# cnc.net
KiCad netlist of a schematic drawn in EAGLE
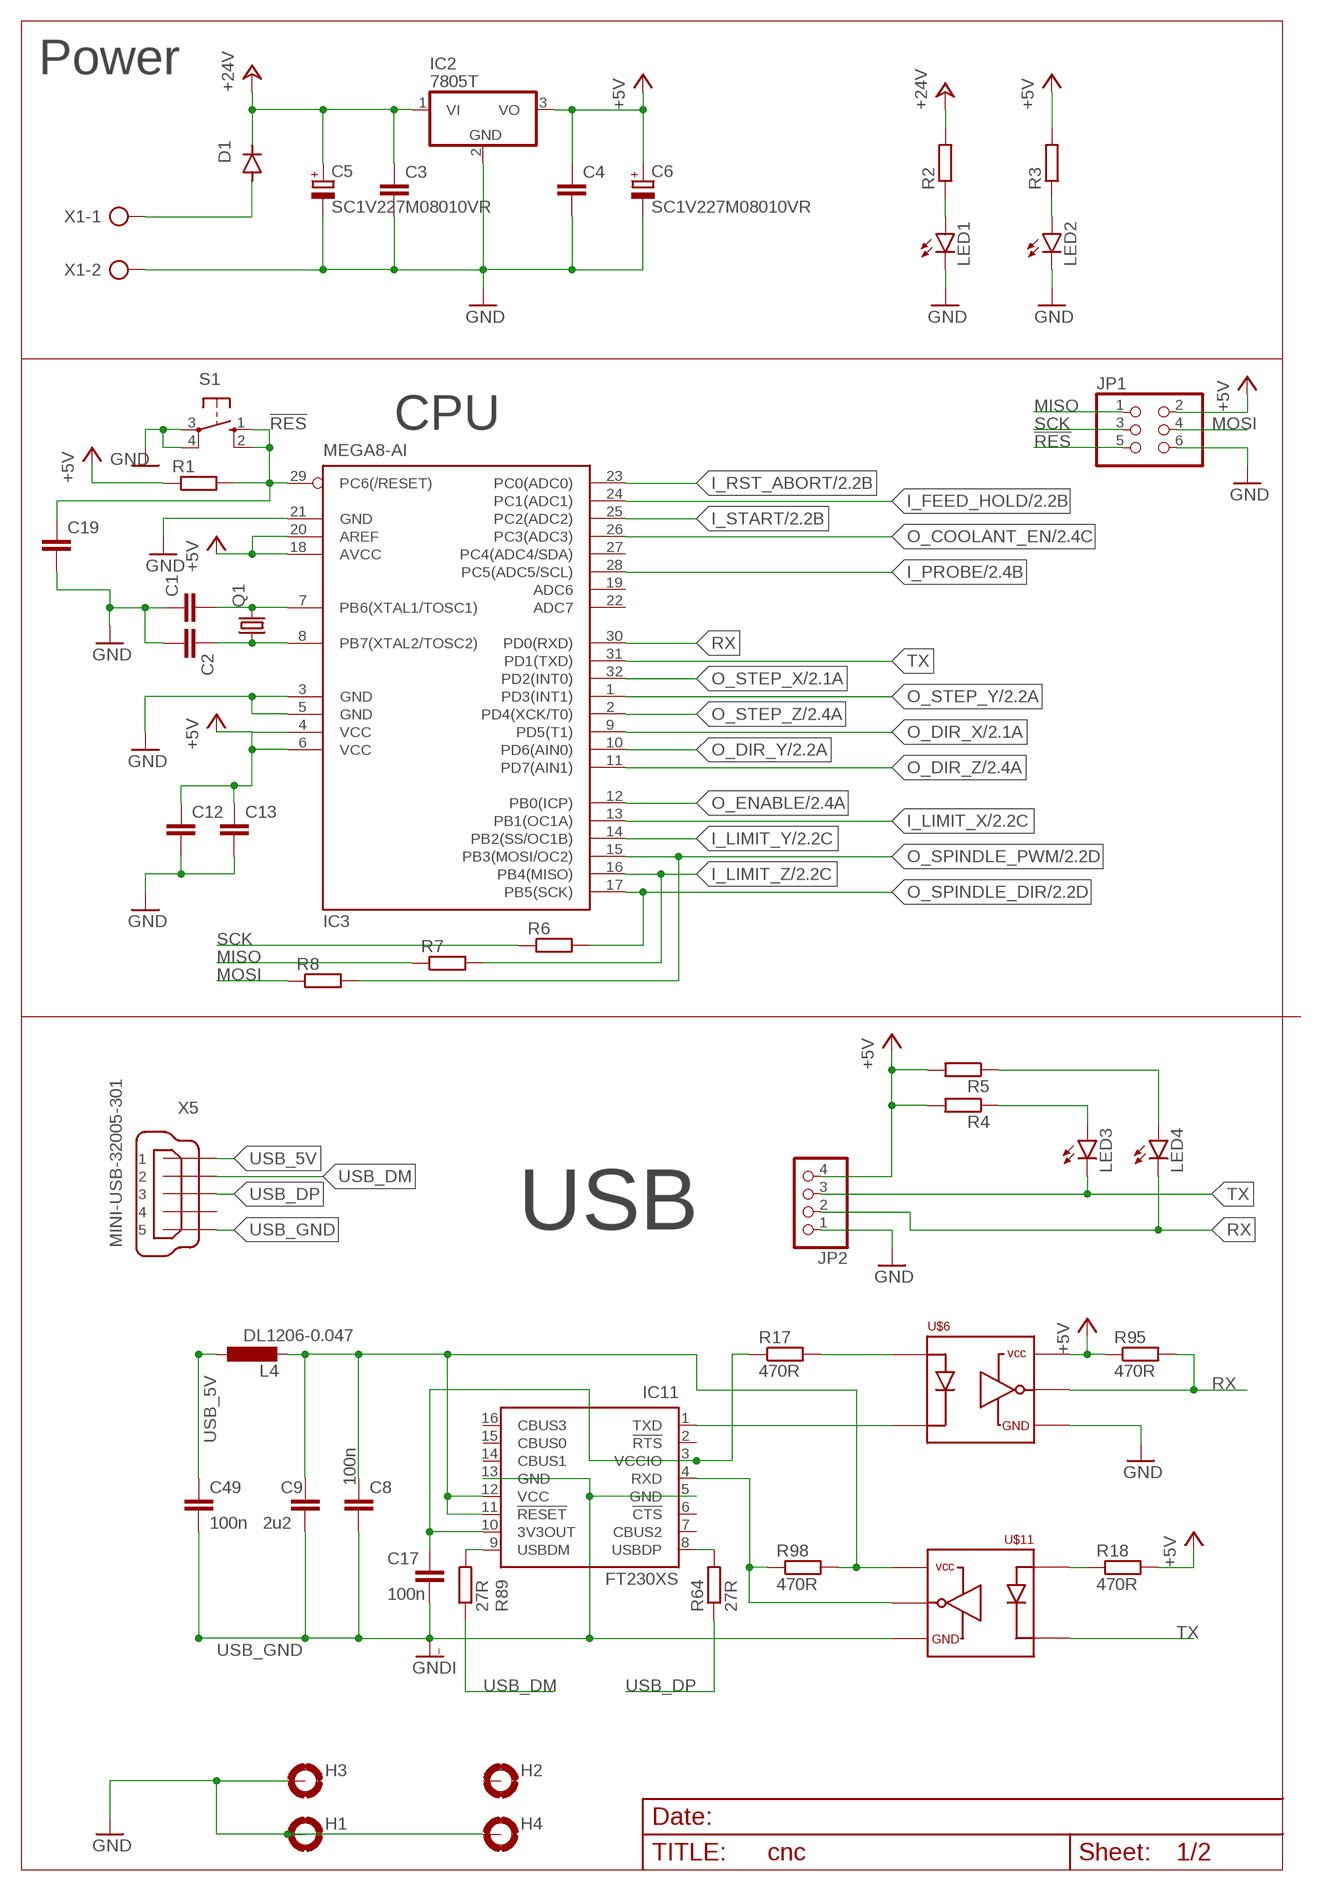
[diagram p0: schematic, sheet 1]
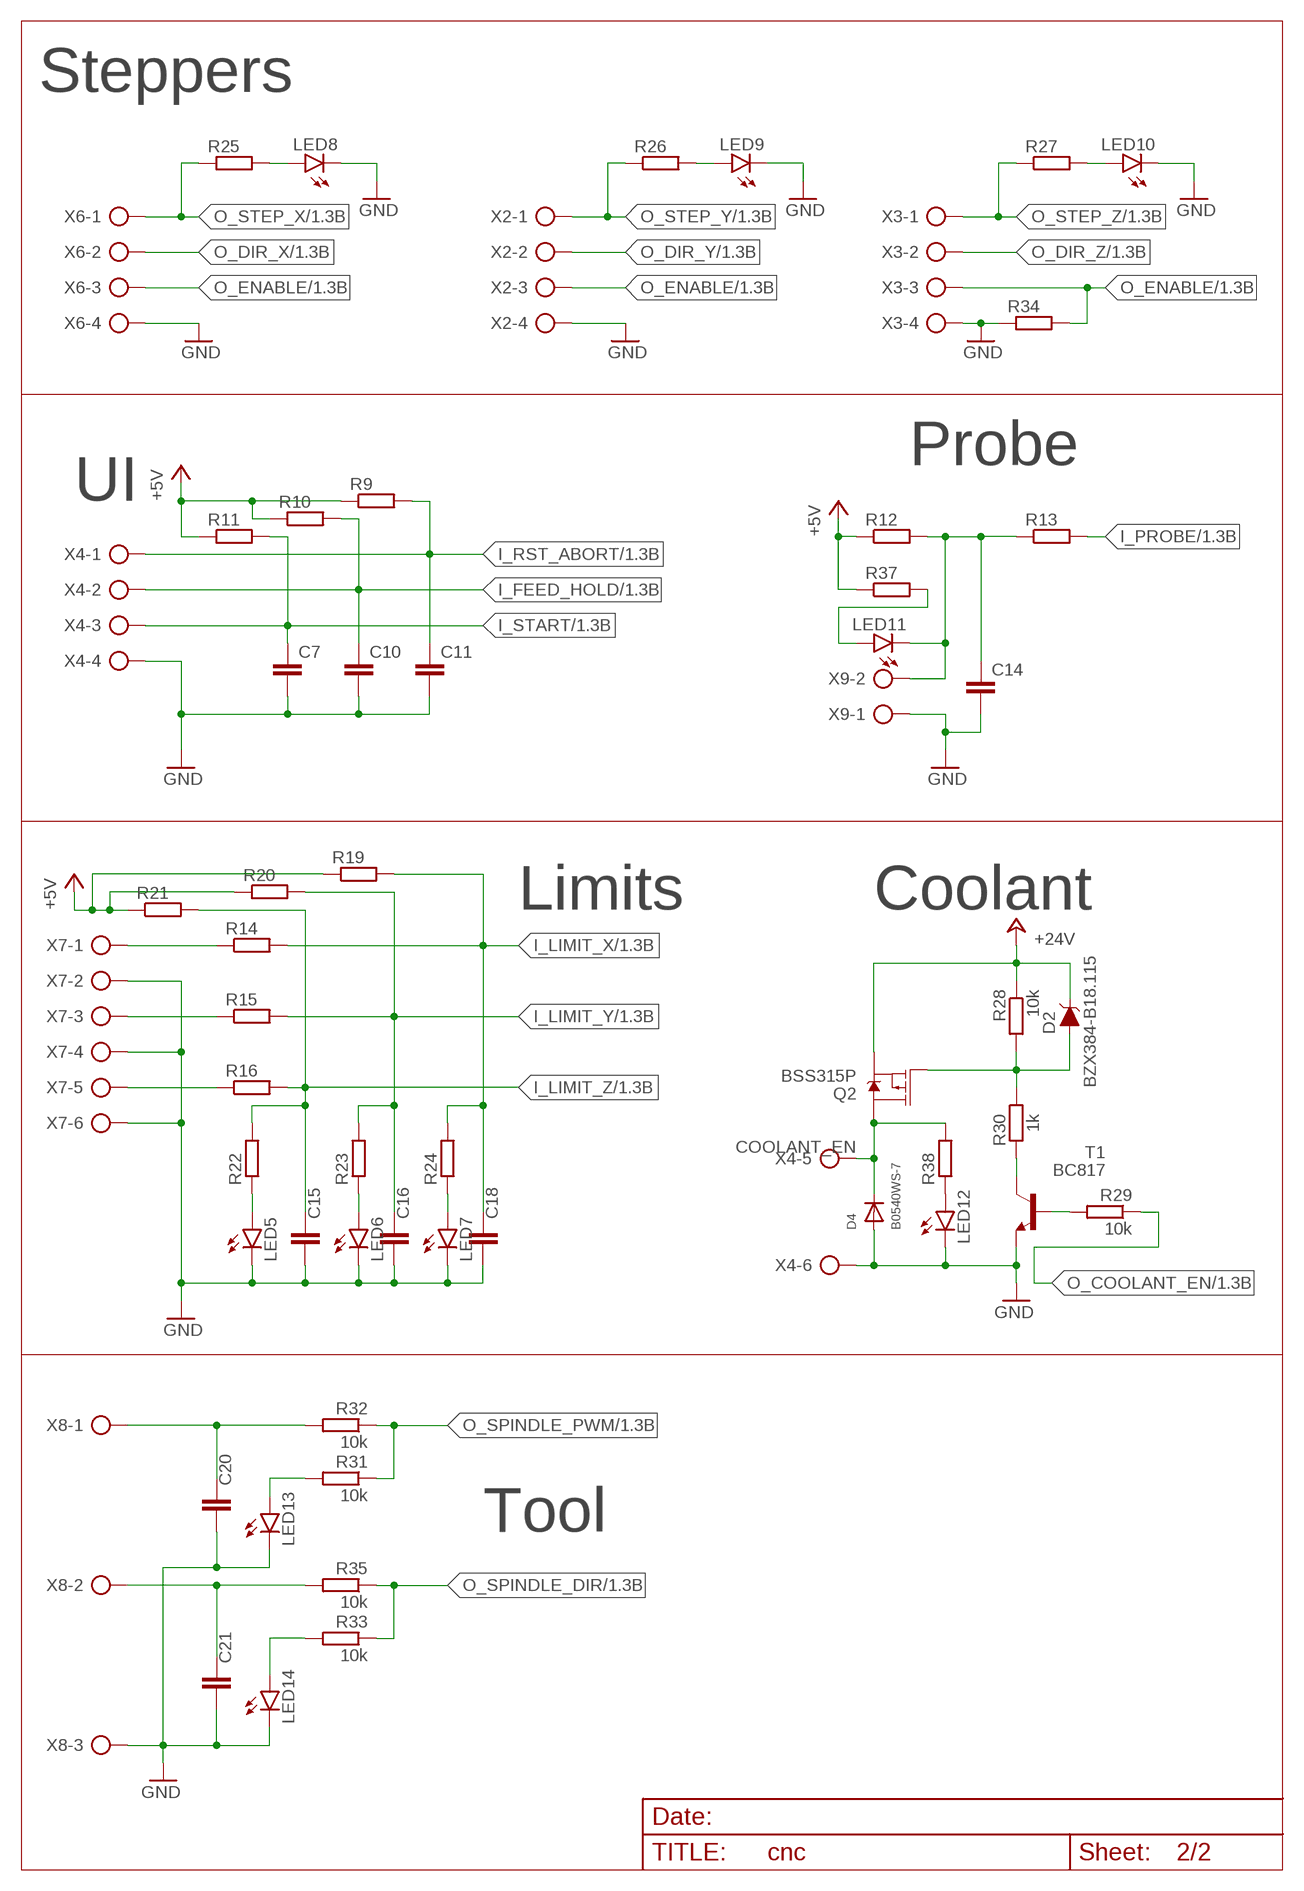
[diagram p1: schematic, sheet 2]

(export (version "E")
  (design (tool "Eeschema 10.0.6"))
  (components
    (comp (ref "C7")
      (value "C-EUC0603")
      (footprint "eagle-import:C0603")
      (libsource (lib "eagle-import") (part "rcl_334_C-EUC0603"))
    )
    (comp (ref "C10")
      (value "C-EUC0603")
      (footprint "eagle-import:C0603")
      (libsource (lib "eagle-import") (part "rcl_334_C-EUC0603"))
    )
    (comp (ref "C11")
      (value "C-EUC0603")
      (footprint "eagle-import:C0603")
      (libsource (lib "eagle-import") (part "rcl_334_C-EUC0603"))
    )
    (comp (ref "C14")
      (value "C-EUC0603")
      (footprint "eagle-import:C0603")
      (libsource (lib "eagle-import") (part "rcl_334_C-EUC0603"))
    )
    (comp (ref "C15")
      (value "C-EUC0603")
      (footprint "eagle-import:C0603")
      (libsource (lib "eagle-import") (part "rcl_334_C-EUC0603"))
    )
    (comp (ref "C16")
      (value "C-EUC0603")
      (footprint "eagle-import:C0603")
      (libsource (lib "eagle-import") (part "rcl_334_C-EUC0603"))
    )
    (comp (ref "C18")
      (value "C-EUC0603")
      (footprint "eagle-import:C0603")
      (libsource (lib "eagle-import") (part "rcl_334_C-EUC0603"))
    )
    (comp (ref "C20")
      (value "C-EUC0603")
      (footprint "eagle-import:C0603")
      (libsource (lib "eagle-import") (part "rcl_334_C-EUC0603"))
    )
    (comp (ref "C21")
      (value "C-EUC0603")
      (footprint "eagle-import:C0603")
      (libsource (lib "eagle-import") (part "rcl_334_C-EUC0603"))
    )
    (comp (ref "D2")
      (value "BZX384-B18.115")
      (footprint "eagle-import:SOD-323")
      (libsource (lib "eagle-import") (part "DIODE-ZENER-BZT52C3V6S"))
    )
    (comp (ref "D4")
      (value "B0540WS-7")
      (footprint "eagle-import:SOD-323F")
      (libsource (lib "eagle-import") (part "DIODESOD-323F"))
    )
    (comp (ref "LED5")
      (value "LEDCHIPLED_0603")
      (footprint "eagle-import:CHIPLED_0603")
      (libsource (lib "eagle-import") (part "LEDCHIPLED_0603"))
    )
    (comp (ref "LED6")
      (value "LEDCHIPLED_0603")
      (footprint "eagle-import:CHIPLED_0603")
      (libsource (lib "eagle-import") (part "LEDCHIPLED_0603"))
    )
    (comp (ref "LED7")
      (value "LEDCHIPLED_0603")
      (footprint "eagle-import:CHIPLED_0603")
      (libsource (lib "eagle-import") (part "LEDCHIPLED_0603"))
    )
    (comp (ref "LED8")
      (value "LEDCHIPLED_0603")
      (footprint "eagle-import:CHIPLED_0603")
      (libsource (lib "eagle-import") (part "LEDCHIPLED_0603"))
    )
    (comp (ref "LED9")
      (value "LEDCHIPLED_0603")
      (footprint "eagle-import:CHIPLED_0603")
      (libsource (lib "eagle-import") (part "LEDCHIPLED_0603"))
    )
    (comp (ref "LED10")
      (value "LEDCHIPLED_0603")
      (footprint "eagle-import:CHIPLED_0603")
      (libsource (lib "eagle-import") (part "LEDCHIPLED_0603"))
    )
    (comp (ref "LED11")
      (value "LEDCHIPLED_0603")
      (footprint "eagle-import:CHIPLED_0603")
      (libsource (lib "eagle-import") (part "LEDCHIPLED_0603"))
    )
    (comp (ref "LED12")
      (value "LEDCHIPLED_0603")
      (footprint "eagle-import:CHIPLED_0603")
      (libsource (lib "eagle-import") (part "LEDCHIPLED_0603"))
    )
    (comp (ref "LED13")
      (value "LEDCHIPLED_0603")
      (footprint "eagle-import:CHIPLED_0603")
      (libsource (lib "eagle-import") (part "LEDCHIPLED_0603"))
    )
    (comp (ref "LED14")
      (value "LEDCHIPLED_0603")
      (footprint "eagle-import:CHIPLED_0603")
      (libsource (lib "eagle-import") (part "LEDCHIPLED_0603"))
    )
    (comp (ref "Q2")
      (value "BSS315P")
      (footprint "eagle-import:SOT23-3")
      (libsource (lib "eagle-import") (part "MOSFET_PCH-DMG2307L"))
    )
    (comp (ref "R9")
      (value "R-EU_R0603")
      (footprint "eagle-import:R0603")
      (libsource (lib "eagle-import") (part "rcl_334_R-EU_R0603"))
    )
    (comp (ref "R10")
      (value "R-EU_R0603")
      (footprint "eagle-import:R0603")
      (libsource (lib "eagle-import") (part "rcl_334_R-EU_R0603"))
    )
    (comp (ref "R11")
      (value "R-EU_R0603")
      (footprint "eagle-import:R0603")
      (libsource (lib "eagle-import") (part "rcl_334_R-EU_R0603"))
    )
    (comp (ref "R12")
      (value "R-EU_R0603")
      (footprint "eagle-import:R0603")
      (libsource (lib "eagle-import") (part "rcl_334_R-EU_R0603"))
    )
    (comp (ref "R13")
      (value "R-EU_R0603")
      (footprint "eagle-import:R0603")
      (libsource (lib "eagle-import") (part "rcl_334_R-EU_R0603"))
    )
    (comp (ref "R14")
      (value "R-EU_R0603")
      (footprint "eagle-import:R0603")
      (libsource (lib "eagle-import") (part "rcl_334_R-EU_R0603"))
    )
    (comp (ref "R15")
      (value "R-EU_R0603")
      (footprint "eagle-import:R0603")
      (libsource (lib "eagle-import") (part "rcl_334_R-EU_R0603"))
    )
    (comp (ref "R16")
      (value "R-EU_R0603")
      (footprint "eagle-import:R0603")
      (libsource (lib "eagle-import") (part "rcl_334_R-EU_R0603"))
    )
    (comp (ref "R19")
      (value "R-EU_R0603")
      (footprint "eagle-import:R0603")
      (libsource (lib "eagle-import") (part "rcl_334_R-EU_R0603"))
    )
    (comp (ref "R20")
      (value "R-EU_R0603")
      (footprint "eagle-import:R0603")
      (libsource (lib "eagle-import") (part "rcl_334_R-EU_R0603"))
    )
    (comp (ref "R21")
      (value "R-EU_R0603")
      (footprint "eagle-import:R0603")
      (libsource (lib "eagle-import") (part "rcl_334_R-EU_R0603"))
    )
    (comp (ref "R22")
      (value "R-EU_R0603")
      (footprint "eagle-import:R0603")
      (libsource (lib "eagle-import") (part "rcl_334_R-EU_R0603"))
    )
    (comp (ref "R23")
      (value "R-EU_R0603")
      (footprint "eagle-import:R0603")
      (libsource (lib "eagle-import") (part "rcl_334_R-EU_R0603"))
    )
    (comp (ref "R24")
      (value "R-EU_R0603")
      (footprint "eagle-import:R0603")
      (libsource (lib "eagle-import") (part "rcl_334_R-EU_R0603"))
    )
    (comp (ref "R25")
      (value "R-EU_R0603")
      (footprint "eagle-import:R0603")
      (libsource (lib "eagle-import") (part "rcl_334_R-EU_R0603"))
    )
    (comp (ref "R26")
      (value "R-EU_R0603")
      (footprint "eagle-import:R0603")
      (libsource (lib "eagle-import") (part "rcl_334_R-EU_R0603"))
    )
    (comp (ref "R27")
      (value "R-EU_R0603")
      (footprint "eagle-import:R0603")
      (libsource (lib "eagle-import") (part "rcl_334_R-EU_R0603"))
    )
    (comp (ref "R28")
      (value "10k")
      (footprint "eagle-import:R0603")
      (libsource (lib "eagle-import") (part "R-EU_R0603"))
    )
    (comp (ref "R29")
      (value "10k")
      (footprint "eagle-import:R0603")
      (libsource (lib "eagle-import") (part "R-EU_R0603"))
    )
    (comp (ref "R30")
      (value "1k")
      (footprint "eagle-import:R0603")
      (libsource (lib "eagle-import") (part "R-EU_R0603"))
    )
    (comp (ref "R31")
      (value "10k")
      (footprint "eagle-import:R0603")
      (libsource (lib "eagle-import") (part "R-EU_R0603"))
    )
    (comp (ref "R32")
      (value "10k")
      (footprint "eagle-import:R0603")
      (libsource (lib "eagle-import") (part "R-EU_R0603"))
    )
    (comp (ref "R33")
      (value "10k")
      (footprint "eagle-import:R0603")
      (libsource (lib "eagle-import") (part "R-EU_R0603"))
    )
    (comp (ref "R34")
      (value "R-EU_R0603")
      (footprint "eagle-import:R0603")
      (libsource (lib "eagle-import") (part "rcl_334_R-EU_R0603"))
    )
    (comp (ref "R35")
      (value "10k")
      (footprint "eagle-import:R0603")
      (libsource (lib "eagle-import") (part "R-EU_R0603"))
    )
    (comp (ref "R37")
      (value "R-EU_R0603")
      (footprint "eagle-import:R0603")
      (libsource (lib "eagle-import") (part "rcl_334_R-EU_R0603"))
    )
    (comp (ref "R38")
      (value "R-EU_R0603")
      (footprint "eagle-import:R0603")
      (libsource (lib "eagle-import") (part "rcl_334_R-EU_R0603"))
    )
    (comp (ref "T1")
      (value "BC817")
      (footprint "eagle-import:SOT23-BEC")
      (libsource (lib "eagle-import") (part "-NPN-SOT23-BECBC817-16"))
    )
    (comp (ref "X2")
      (value "AK500/4")
      (footprint "eagle-import:AK500_4")
      (libsource (lib "eagle-import") (part "AK500/4"))
    )
    (comp (ref "X3")
      (value "AK500/4")
      (footprint "eagle-import:AK500_4")
      (libsource (lib "eagle-import") (part "AK500/4"))
    )
    (comp (ref "X4")
      (value "AK500/6")
      (footprint "eagle-import:AK500_6")
      (libsource (lib "eagle-import") (part "AK500/6"))
    )
    (comp (ref "X6")
      (value "AK500/4")
      (footprint "eagle-import:AK500_4")
      (libsource (lib "eagle-import") (part "AK500/4"))
    )
    (comp (ref "X7")
      (value "AK500/6")
      (footprint "eagle-import:AK500_6")
      (libsource (lib "eagle-import") (part "AK500/6"))
    )
    (comp (ref "X8")
      (value "AK500/3")
      (footprint "eagle-import:AK500_3")
      (libsource (lib "eagle-import") (part "AK500/3"))
    )
    (comp (ref "X9")
      (value "AK500/2")
      (footprint "eagle-import:AK500_2")
      (libsource (lib "eagle-import") (part "AK500/2"))
    )
    (comp (ref "C1")
      (value "C-EUC0603")
      (footprint "eagle-import:C0603")
      (libsource (lib "eagle-import") (part "rcl_334_C-EUC0603"))
    )
    (comp (ref "C2")
      (value "C-EUC0603")
      (footprint "eagle-import:C0603")
      (libsource (lib "eagle-import") (part "rcl_334_C-EUC0603"))
    )
    (comp (ref "C3")
      (value "C-EUC0603")
      (footprint "eagle-import:C0603")
      (libsource (lib "eagle-import") (part "rcl_334_C-EUC0603"))
    )
    (comp (ref "C4")
      (value "C-EUC0603")
      (footprint "eagle-import:C0603")
      (libsource (lib "eagle-import") (part "rcl_334_C-EUC0603"))
    )
    (comp (ref "C5")
      (value "SC1V227M08010VR")
      (footprint "eagle-import:150CLZ-0810")
      (libsource (lib "eagle-import") (part "CPOL-EU150CLZ-0810"))
    )
    (comp (ref "C6")
      (value "SC1V227M08010VR")
      (footprint "eagle-import:150CLZ-0810")
      (libsource (lib "eagle-import") (part "CPOL-EU150CLZ-0810"))
    )
    (comp (ref "C8")
      (value "100n")
      (footprint "eagle-import:C0603")
      (libsource (lib "eagle-import") (part "C-EUC0603"))
    )
    (comp (ref "C9")
      (value "2u2")
      (footprint "eagle-import:C0603")
      (libsource (lib "eagle-import") (part "C-EUC0603"))
    )
    (comp (ref "C12")
      (value "C-EUC0603")
      (footprint "eagle-import:C0603")
      (libsource (lib "eagle-import") (part "rcl_334_C-EUC0603"))
    )
    (comp (ref "C13")
      (value "C-EUC0603")
      (footprint "eagle-import:C0603")
      (libsource (lib "eagle-import") (part "rcl_334_C-EUC0603"))
    )
    (comp (ref "C17")
      (value "100n")
      (footprint "eagle-import:C0603")
      (libsource (lib "eagle-import") (part "C-EUC0603"))
    )
    (comp (ref "C19")
      (value "C-EUC0603")
      (footprint "eagle-import:C0603")
      (libsource (lib "eagle-import") (part "rcl_334_C-EUC0603"))
    )
    (comp (ref "C49")
      (value "100n")
      (footprint "eagle-import:C0603")
      (libsource (lib "eagle-import") (part "C-EUC0603"))
    )
    (comp (ref "D1")
      (value "DIODE-DO-214AC")
      (footprint "eagle-import:DO-214AC")
      (libsource (lib "eagle-import") (part "DIODE-DO-214AC"))
    )
    (comp (ref "H1")
      (value "MOUNT-PAD-ROUND3.0")
      (footprint "eagle-import:3,0-PAD")
      (libsource (lib "eagle-import") (part "MOUNT-PAD-ROUND3.0"))
    )
    (comp (ref "H2")
      (value "MOUNT-PAD-ROUND3.0")
      (footprint "eagle-import:3,0-PAD")
      (libsource (lib "eagle-import") (part "MOUNT-PAD-ROUND3.0"))
    )
    (comp (ref "H3")
      (value "MOUNT-PAD-ROUND3.0")
      (footprint "eagle-import:3,0-PAD")
      (libsource (lib "eagle-import") (part "MOUNT-PAD-ROUND3.0"))
    )
    (comp (ref "H4")
      (value "MOUNT-PAD-ROUND3.0")
      (footprint "eagle-import:3,0-PAD")
      (libsource (lib "eagle-import") (part "MOUNT-PAD-ROUND3.0"))
    )
    (comp (ref "IC2")
      (value "7805T")
      (footprint "eagle-import:TO220H")
      (libsource (lib "eagle-import") (part "78T05"))
    )
    (comp (ref "IC3")
      (value "MEGA8-AI")
      (footprint "eagle-import:TQFP32-08")
      (fields (field (name "MPN") "ATMEGA8-16AU"))
      (libsource (lib "eagle-import") (part "MEGA8-AI"))
    )
    (comp (ref "IC11")
      (value "FT230XS")
      (footprint "eagle-import:SSOP16")
      (libsource (lib "eagle-import") (part "FT230XS"))
    )
    (comp (ref "JP1")
      (value "PINHD-2X3")
      (footprint "eagle-import:2X03")
      (libsource (lib "eagle-import") (part "PINHD-2X3"))
    )
    (comp (ref "JP2")
      (value "PINHD-1X4")
      (footprint "eagle-import:1X04")
      (libsource (lib "eagle-import") (part "PINHD-1X4"))
    )
    (comp (ref "L4")
      (value "DL1206-0.047")
      (footprint "eagle-import:L3225P")
      (libsource (lib "eagle-import") (part "L-EUL3225P"))
    )
    (comp (ref "LED1")
      (value "LEDCHIPLED_0805")
      (footprint "eagle-import:CHIPLED_0805")
      (libsource (lib "eagle-import") (part "LEDCHIPLED_0805"))
    )
    (comp (ref "LED2")
      (value "LEDCHIPLED_0805")
      (footprint "eagle-import:CHIPLED_0805")
      (libsource (lib "eagle-import") (part "LEDCHIPLED_0805"))
    )
    (comp (ref "LED3")
      (value "LEDCHIPLED_0603")
      (footprint "eagle-import:CHIPLED_0603")
      (libsource (lib "eagle-import") (part "LEDCHIPLED_0603"))
    )
    (comp (ref "LED4")
      (value "LEDCHIPLED_0603")
      (footprint "eagle-import:CHIPLED_0603")
      (libsource (lib "eagle-import") (part "LEDCHIPLED_0603"))
    )
    (comp (ref "Q1")
      (value "CRYSTALHC49S")
      (footprint "eagle-import:HC49_S")
      (libsource (lib "eagle-import") (part "CRYSTALHC49S"))
    )
    (comp (ref "R1")
      (value "R-EU_R0603")
      (footprint "eagle-import:R0603")
      (libsource (lib "eagle-import") (part "rcl_334_R-EU_R0603"))
    )
    (comp (ref "R2")
      (value "R-EU_R0603")
      (footprint "eagle-import:R0603")
      (libsource (lib "eagle-import") (part "rcl_334_R-EU_R0603"))
    )
    (comp (ref "R3")
      (value "R-EU_R0603")
      (footprint "eagle-import:R0603")
      (libsource (lib "eagle-import") (part "rcl_334_R-EU_R0603"))
    )
    (comp (ref "R4")
      (value "R-EU_R0603")
      (footprint "eagle-import:R0603")
      (libsource (lib "eagle-import") (part "rcl_334_R-EU_R0603"))
    )
    (comp (ref "R5")
      (value "R-EU_R0603")
      (footprint "eagle-import:R0603")
      (libsource (lib "eagle-import") (part "rcl_334_R-EU_R0603"))
    )
    (comp (ref "R6")
      (value "R-EU_R0603")
      (footprint "eagle-import:R0603")
      (libsource (lib "eagle-import") (part "rcl_334_R-EU_R0603"))
    )
    (comp (ref "R7")
      (value "R-EU_R0603")
      (footprint "eagle-import:R0603")
      (libsource (lib "eagle-import") (part "rcl_334_R-EU_R0603"))
    )
    (comp (ref "R8")
      (value "R-EU_R0603")
      (footprint "eagle-import:R0603")
      (libsource (lib "eagle-import") (part "rcl_334_R-EU_R0603"))
    )
    (comp (ref "R17")
      (value "470R")
      (footprint "eagle-import:R0603")
      (libsource (lib "eagle-import") (part "R-EU_R0603"))
    )
    (comp (ref "R18")
      (value "470R")
      (footprint "eagle-import:R0603")
      (libsource (lib "eagle-import") (part "R-EU_R0603"))
    )
    (comp (ref "R64")
      (value "27R")
      (footprint "eagle-import:R0603")
      (libsource (lib "eagle-import") (part "R-EU_R0603"))
    )
    (comp (ref "R89")
      (value "27R")
      (footprint "eagle-import:R0603")
      (libsource (lib "eagle-import") (part "R-EU_R0603"))
    )
    (comp (ref "R95")
      (value "470R")
      (footprint "eagle-import:R0603")
      (libsource (lib "eagle-import") (part "R-EU_R0603"))
    )
    (comp (ref "R98")
      (value "470R")
      (footprint "eagle-import:R0603")
      (libsource (lib "eagle-import") (part "R-EU_R0603"))
    )
    (comp (ref "S1")
      (value "10-XX")
      (footprint "eagle-import:B3F-10XX")
      (fields (field (name "MPN") "B3F-1000"))
      (libsource (lib "eagle-import") (part "10-XX"))
    )
    (comp (ref "U$6")
      (value "TLP2362")
      (footprint "eagle-import:SO-6")
      (libsource (lib "eagle-import") (part "TPL2362"))
    )
    (comp (ref "U$11")
      (value "TLP2362")
      (footprint "eagle-import:SO-6")
      (libsource (lib "eagle-import") (part "TPL2362"))
    )
    (comp (ref "X1")
      (value "AK500/2")
      (footprint "eagle-import:AK500_2")
      (libsource (lib "eagle-import") (part "AK500/2"))
    )
    (comp (ref "X5")
      (value "MINI-USB-32005-301")
      (footprint "eagle-import:32005-301")
      (libsource (lib "eagle-import") (part "MINI-USB-32005-301"))
    )
  )
  (nets
    (net (code "1") (name "+5V") (class "Default")
      (node (ref "C12") (pin "1") (pinfunction "1_1") (pintype "passive"))
      (node (ref "C13") (pin "1") (pinfunction "1_1") (pintype "passive"))
      (node (ref "C4") (pin "1") (pinfunction "1_1") (pintype "passive"))
      (node (ref "C6") (pin "+") (pinfunction "+_+") (pintype "passive"))
      (node (ref "IC2") (pin "3") (pinfunction "VO_3") (pintype "passive"))
      (node (ref "IC3") (pin "18") (pinfunction "AVCC_18") (pintype "power_in"))
      (node (ref "IC3") (pin "20") (pinfunction "AREF_20") (pintype "passive"))
      (node (ref "IC3") (pin "4") (pinfunction "VCC_4") (pintype "power_in"))
      (node (ref "IC3") (pin "6") (pinfunction "VCC_6") (pintype "power_in"))
      (node (ref "JP1") (pin "2") (pinfunction "2_2") (pintype "passive"))
      (node (ref "JP2") (pin "4") (pinfunction "4_4") (pintype "passive"))
      (node (ref "R1") (pin "1") (pinfunction "1_1") (pintype "passive"))
      (node (ref "R10") (pin "1") (pinfunction "1_1") (pintype "passive"))
      (node (ref "R11") (pin "1") (pinfunction "1_1") (pintype "passive"))
      (node (ref "R12") (pin "1") (pinfunction "1_1") (pintype "passive"))
      (node (ref "R18") (pin "2") (pinfunction "2_2") (pintype "passive"))
      (node (ref "R19") (pin "1") (pinfunction "1_1") (pintype "passive"))
      (node (ref "R20") (pin "1") (pinfunction "1_1") (pintype "passive"))
      (node (ref "R21") (pin "1") (pinfunction "1_1") (pintype "passive"))
      (node (ref "R3") (pin "2") (pinfunction "2_2") (pintype "passive"))
      (node (ref "R37") (pin "1") (pinfunction "1_1") (pintype "passive"))
      (node (ref "R4") (pin "2") (pinfunction "2_2") (pintype "passive"))
      (node (ref "R5") (pin "2") (pinfunction "2_2") (pintype "passive"))
      (node (ref "R9") (pin "1") (pinfunction "1_1") (pintype "passive"))
      (node (ref "R95") (pin "1") (pinfunction "1_1") (pintype "passive"))
      (node (ref "U$6") (pin "6") (pinfunction "6_6") (pintype "bidirectional"))
    )
    (net (code "2") (name "+24V") (class "Default")
      (node (ref "C3") (pin "1") (pinfunction "1_1") (pintype "passive"))
      (node (ref "C5") (pin "+") (pinfunction "+_+") (pintype "passive"))
      (node (ref "D1") (pin "C") (pinfunction "C_C") (pintype "passive"))
      (node (ref "D2") (pin "C") (pinfunction "C_C") (pintype "passive"))
      (node (ref "IC2") (pin "1") (pinfunction "VI_1") (pintype "input"))
      (node (ref "Q2") (pin "2") (pinfunction "S_2") (pintype "bidirectional"))
      (node (ref "R2") (pin "2") (pinfunction "2_2") (pintype "passive"))
      (node (ref "R28") (pin "1") (pinfunction "1_1") (pintype "passive"))
    )
    (net (code "3") (name "COOLANT_EN") (class "Default")
      (node (ref "D4") (pin "C") (pinfunction "C_C") (pintype "passive"))
      (node (ref "Q2") (pin "3") (pinfunction "D_3") (pintype "bidirectional"))
      (node (ref "R38") (pin "2") (pinfunction "2_2") (pintype "passive"))
      (node (ref "X4") (pin "5") (pinfunction "KL_5") (pintype "passive"))
    )
    (net (code "4") (name "GND") (class "Default")
      (node (ref "C1") (pin "1") (pinfunction "1_1") (pintype "passive"))
      (node (ref "C10") (pin "2") (pinfunction "2_2") (pintype "passive"))
      (node (ref "C11") (pin "2") (pinfunction "2_2") (pintype "passive"))
      (node (ref "C12") (pin "2") (pinfunction "2_2") (pintype "passive"))
      (node (ref "C13") (pin "2") (pinfunction "2_2") (pintype "passive"))
      (node (ref "C14") (pin "2") (pinfunction "2_2") (pintype "passive"))
      (node (ref "C15") (pin "2") (pinfunction "2_2") (pintype "passive"))
      (node (ref "C16") (pin "2") (pinfunction "2_2") (pintype "passive"))
      (node (ref "C18") (pin "2") (pinfunction "2_2") (pintype "passive"))
      (node (ref "C19") (pin "2") (pinfunction "2_2") (pintype "passive"))
      (node (ref "C2") (pin "2") (pinfunction "2_2") (pintype "passive"))
      (node (ref "C20") (pin "2") (pinfunction "2_2") (pintype "passive"))
      (node (ref "C21") (pin "2") (pinfunction "2_2") (pintype "passive"))
      (node (ref "C3") (pin "2") (pinfunction "2_2") (pintype "passive"))
      (node (ref "C4") (pin "2") (pinfunction "2_2") (pintype "passive"))
      (node (ref "C5") (pin "-") (pinfunction "-_-") (pintype "passive"))
      (node (ref "C6") (pin "-") (pinfunction "-_-") (pintype "passive"))
      (node (ref "C7") (pin "2") (pinfunction "2_2") (pintype "passive"))
      (node (ref "D4") (pin "A") (pinfunction "A_A") (pintype "passive"))
      (node (ref "H1") (pin "B3,0") (pinfunction "MOUNT_B3,0") (pintype "passive"))
      (node (ref "H3") (pin "B3,0") (pinfunction "MOUNT_B3,0") (pintype "passive"))
      (node (ref "H4") (pin "B3,0") (pinfunction "MOUNT_B3,0") (pintype "passive"))
      (node (ref "IC2") (pin "2") (pinfunction "GND_2") (pintype "passive"))
      (node (ref "IC3") (pin "21") (pinfunction "GND_21") (pintype "power_in"))
      (node (ref "IC3") (pin "3") (pinfunction "GND_3") (pintype "power_in"))
      (node (ref "IC3") (pin "5") (pinfunction "GND_5") (pintype "power_in"))
      (node (ref "JP1") (pin "6") (pinfunction "6_6") (pintype "passive"))
      (node (ref "JP2") (pin "1") (pinfunction "1_1") (pintype "passive"))
      (node (ref "LED1") (pin "C") (pinfunction "C_C") (pintype "passive"))
      (node (ref "LED10") (pin "C") (pinfunction "C_C") (pintype "passive"))
      (node (ref "LED12") (pin "C") (pinfunction "C_C") (pintype "passive"))
      (node (ref "LED13") (pin "C") (pinfunction "C_C") (pintype "passive"))
      (node (ref "LED14") (pin "C") (pinfunction "C_C") (pintype "passive"))
      (node (ref "LED2") (pin "C") (pinfunction "C_C") (pintype "passive"))
      (node (ref "LED5") (pin "C") (pinfunction "C_C") (pintype "passive"))
      (node (ref "LED6") (pin "C") (pinfunction "C_C") (pintype "passive"))
      (node (ref "LED7") (pin "C") (pinfunction "C_C") (pintype "passive"))
      (node (ref "LED8") (pin "C") (pinfunction "C_C") (pintype "passive"))
      (node (ref "LED9") (pin "C") (pinfunction "C_C") (pintype "passive"))
      (node (ref "R34") (pin "1") (pinfunction "1_1") (pintype "passive"))
      (node (ref "S1") (pin "3") (pinfunction "P_3") (pintype "passive"))
      (node (ref "S1") (pin "4") (pinfunction "P1_4") (pintype "passive"))
      (node (ref "T1") (pin "E") (pinfunction "E_E") (pintype "passive"))
      (node (ref "U$6") (pin "4") (pinfunction "4_4") (pintype "bidirectional"))
      (node (ref "X1") (pin "2") (pinfunction "KL_2") (pintype "passive"))
      (node (ref "X2") (pin "4") (pinfunction "KL_4") (pintype "passive"))
      (node (ref "X3") (pin "4") (pinfunction "KL_4") (pintype "passive"))
      (node (ref "X4") (pin "4") (pinfunction "KL_4") (pintype "passive"))
      (node (ref "X4") (pin "6") (pinfunction "KL_6") (pintype "passive"))
      (node (ref "X6") (pin "4") (pinfunction "KL_4") (pintype "passive"))
      (node (ref "X7") (pin "2") (pinfunction "KL_2") (pintype "passive"))
      (node (ref "X7") (pin "4") (pinfunction "KL_4") (pintype "passive"))
      (node (ref "X7") (pin "6") (pinfunction "KL_6") (pintype "passive"))
      (node (ref "X8") (pin "3") (pinfunction "KL_3") (pintype "passive"))
      (node (ref "X9") (pin "1") (pinfunction "KL_1") (pintype "passive"))
    )
    (net (code "5") (name "I_FEED_HOLD") (class "Default")
      (node (ref "C10") (pin "1") (pinfunction "1_1") (pintype "passive"))
      (node (ref "IC3") (pin "24") (pinfunction "PC1(ADC1)_24") (pintype "bidirectional"))
      (node (ref "R10") (pin "2") (pinfunction "2_2") (pintype "passive"))
      (node (ref "X4") (pin "2") (pinfunction "KL_2") (pintype "passive"))
    )
    (net (code "6") (name "I_LIMIT_X") (class "Default")
      (node (ref "C18") (pin "1") (pinfunction "1_1") (pintype "passive"))
      (node (ref "IC3") (pin "13") (pinfunction "PB1(OC1A)_13") (pintype "bidirectional"))
      (node (ref "R14") (pin "2") (pinfunction "2_2") (pintype "passive"))
      (node (ref "R19") (pin "2") (pinfunction "2_2") (pintype "passive"))
      (node (ref "R24") (pin "2") (pinfunction "2_2") (pintype "passive"))
    )
    (net (code "7") (name "I_LIMIT_Y") (class "Default")
      (node (ref "C16") (pin "1") (pinfunction "1_1") (pintype "passive"))
      (node (ref "IC3") (pin "14") (pinfunction "PB2(SS/OC1B)_14") (pintype "bidirectional"))
      (node (ref "R15") (pin "2") (pinfunction "2_2") (pintype "passive"))
      (node (ref "R20") (pin "2") (pinfunction "2_2") (pintype "passive"))
      (node (ref "R23") (pin "2") (pinfunction "2_2") (pintype "passive"))
    )
    (net (code "8") (name "I_LIMIT_Z") (class "Default")
      (node (ref "C15") (pin "1") (pinfunction "1_1") (pintype "passive"))
      (node (ref "IC3") (pin "16") (pinfunction "PB4(MISO)_16") (pintype "bidirectional"))
      (node (ref "R16") (pin "2") (pinfunction "2_2") (pintype "passive"))
      (node (ref "R21") (pin "2") (pinfunction "2_2") (pintype "passive"))
      (node (ref "R22") (pin "2") (pinfunction "2_2") (pintype "passive"))
      (node (ref "R7") (pin "2") (pinfunction "2_2") (pintype "passive"))
    )
    (net (code "9") (name "I_PROBE") (class "Default")
      (node (ref "IC3") (pin "28") (pinfunction "PC5(ADC5/SCL)_28") (pintype "bidirectional"))
      (node (ref "R13") (pin "2") (pinfunction "2_2") (pintype "passive"))
    )
    (net (code "10") (name "I_RST_ABORT") (class "Default")
      (node (ref "C11") (pin "1") (pinfunction "1_1") (pintype "passive"))
      (node (ref "IC3") (pin "23") (pinfunction "PC0(ADC0)_23") (pintype "bidirectional"))
      (node (ref "R9") (pin "2") (pinfunction "2_2") (pintype "passive"))
      (node (ref "X4") (pin "1") (pinfunction "KL_1") (pintype "passive"))
    )
    (net (code "11") (name "I_START") (class "Default")
      (node (ref "C7") (pin "1") (pinfunction "1_1") (pintype "passive"))
      (node (ref "IC3") (pin "25") (pinfunction "PC2(ADC2)_25") (pintype "bidirectional"))
      (node (ref "R11") (pin "2") (pinfunction "2_2") (pintype "passive"))
      (node (ref "X4") (pin "3") (pinfunction "KL_3") (pintype "passive"))
    )
    (net (code "12") (name "MISO") (class "Default")
      (node (ref "JP1") (pin "1") (pinfunction "1_1") (pintype "passive"))
      (node (ref "R7") (pin "1") (pinfunction "1_1") (pintype "passive"))
    )
    (net (code "13") (name "MOSI") (class "Default")
      (node (ref "JP1") (pin "4") (pinfunction "4_4") (pintype "passive"))
      (node (ref "R8") (pin "1") (pinfunction "1_1") (pintype "passive"))
    )
    (net (code "14") (name "Net-(IC3-PB6(XTAL1{slash}TOSC1))") (class "Default")
      (node (ref "C1") (pin "2") (pinfunction "2_2") (pintype "passive"))
      (node (ref "IC3") (pin "7") (pinfunction "PB6(XTAL1/TOSC1)_7") (pintype "bidirectional"))
      (node (ref "Q1") (pin "2") (pinfunction "2_2") (pintype "passive"))
    )
    (net (code "15") (name "Net-(IC3-PB7(XTAL2{slash}TOSC2))") (class "Default")
      (node (ref "C2") (pin "1") (pinfunction "1_1") (pintype "passive"))
      (node (ref "IC3") (pin "8") (pinfunction "PB7(XTAL2/TOSC2)_8") (pintype "bidirectional"))
      (node (ref "Q1") (pin "1") (pinfunction "1_1") (pintype "passive"))
    )
    (net (code "16") (name "Net-(IC11-3V3OUT)") (class "Default")
      (node (ref "C17") (pin "1") (pinfunction "1_1") (pintype "passive"))
      (node (ref "IC11") (pin "10") (pinfunction "3V3OUT_10") (pintype "output"))
      (node (ref "IC11") (pin "3") (pinfunction "VCCIO_3") (pintype "power_in"))
      (node (ref "R17") (pin "1") (pinfunction "1_1") (pintype "passive"))
    )
    (net (code "17") (name "Net-(IC11-RXD)") (class "Default")
      (node (ref "IC11") (pin "4") (pinfunction "RXD_4") (pintype "input"))
      (node (ref "R98") (pin "1") (pinfunction "1_1") (pintype "passive"))
      (node (ref "U$11") (pin "5") (pinfunction "5_5") (pintype "bidirectional"))
    )
    (net (code "18") (name "Net-(IC11-TXD)") (class "Default")
      (node (ref "IC11") (pin "1") (pinfunction "TXD_1") (pintype "output"))
      (node (ref "U$6") (pin "3") (pinfunction "3_3") (pintype "bidirectional"))
    )
    (net (code "19") (name "Net-(IC11-USBDM)") (class "Default")
      (node (ref "IC11") (pin "9") (pinfunction "USBDM_9") (pintype "input"))
      (node (ref "R89") (pin "2") (pinfunction "2_2") (pintype "passive"))
    )
    (net (code "20") (name "Net-(IC11-USBDP)") (class "Default")
      (node (ref "IC11") (pin "8") (pinfunction "USBDP_8") (pintype "input"))
      (node (ref "R64") (pin "2") (pinfunction "2_2") (pintype "passive"))
    )
    (net (code "21") (name "Net-(IC11-VCC)") (class "Default")
      (node (ref "C8") (pin "1") (pinfunction "1_1") (pintype "passive"))
      (node (ref "C9") (pin "1") (pinfunction "1_1") (pintype "passive"))
      (node (ref "IC11") (pin "11") (pinfunction "~{RESET}_11") (pintype "input"))
      (node (ref "IC11") (pin "12") (pinfunction "VCC_12") (pintype "power_in"))
      (node (ref "L4") (pin "2") (pinfunction "2_2") (pintype "passive"))
      (node (ref "R98") (pin "2") (pinfunction "2_2") (pintype "passive"))
      (node (ref "U$11") (pin "6") (pinfunction "6_6") (pintype "bidirectional"))
    )
    (net (code "22") (name "Net-(LED1-PadA)") (class "Default")
      (node (ref "LED1") (pin "A") (pinfunction "A_A") (pintype "passive"))
      (node (ref "R2") (pin "1") (pinfunction "1_1") (pintype "passive"))
    )
    (net (code "23") (name "Net-(LED2-PadA)") (class "Default")
      (node (ref "LED2") (pin "A") (pinfunction "A_A") (pintype "passive"))
      (node (ref "R3") (pin "1") (pinfunction "1_1") (pintype "passive"))
    )
    (net (code "24") (name "Net-(LED3-PadA)") (class "Default")
      (node (ref "LED3") (pin "A") (pinfunction "A_A") (pintype "passive"))
      (node (ref "R4") (pin "1") (pinfunction "1_1") (pintype "passive"))
    )
    (net (code "25") (name "Net-(LED4-PadA)") (class "Default")
      (node (ref "LED4") (pin "A") (pinfunction "A_A") (pintype "passive"))
      (node (ref "R5") (pin "1") (pinfunction "1_1") (pintype "passive"))
    )
    (net (code "26") (name "Net-(LED5-PadA)") (class "Default")
      (node (ref "LED5") (pin "A") (pinfunction "A_A") (pintype "passive"))
      (node (ref "R22") (pin "1") (pinfunction "1_1") (pintype "passive"))
    )
    (net (code "27") (name "Net-(LED6-PadA)") (class "Default")
      (node (ref "LED6") (pin "A") (pinfunction "A_A") (pintype "passive"))
      (node (ref "R23") (pin "1") (pinfunction "1_1") (pintype "passive"))
    )
    (net (code "28") (name "Net-(LED7-PadA)") (class "Default")
      (node (ref "LED7") (pin "A") (pinfunction "A_A") (pintype "passive"))
      (node (ref "R24") (pin "1") (pinfunction "1_1") (pintype "passive"))
    )
    (net (code "29") (name "Net-(LED8-PadA)") (class "Default")
      (node (ref "LED8") (pin "A") (pinfunction "A_A") (pintype "passive"))
      (node (ref "R25") (pin "2") (pinfunction "2_2") (pintype "passive"))
    )
    (net (code "30") (name "Net-(LED9-PadA)") (class "Default")
      (node (ref "LED9") (pin "A") (pinfunction "A_A") (pintype "passive"))
      (node (ref "R26") (pin "2") (pinfunction "2_2") (pintype "passive"))
    )
    (net (code "31") (name "Net-(LED10-PadA)") (class "Default")
      (node (ref "LED10") (pin "A") (pinfunction "A_A") (pintype "passive"))
      (node (ref "R27") (pin "2") (pinfunction "2_2") (pintype "passive"))
    )
    (net (code "32") (name "Net-(LED11-PadA)") (class "Default")
      (node (ref "LED11") (pin "A") (pinfunction "A_A") (pintype "passive"))
      (node (ref "R37") (pin "2") (pinfunction "2_2") (pintype "passive"))
    )
    (net (code "33") (name "Net-(LED12-PadA)") (class "Default")
      (node (ref "LED12") (pin "A") (pinfunction "A_A") (pintype "passive"))
      (node (ref "R38") (pin "1") (pinfunction "1_1") (pintype "passive"))
    )
    (net (code "34") (name "Net-(LED13-PadA)") (class "Default")
      (node (ref "LED13") (pin "A") (pinfunction "A_A") (pintype "passive"))
      (node (ref "R31") (pin "2") (pinfunction "2_2") (pintype "passive"))
    )
    (net (code "35") (name "Net-(LED14-PadA)") (class "Default")
      (node (ref "LED14") (pin "A") (pinfunction "A_A") (pintype "passive"))
      (node (ref "R33") (pin "2") (pinfunction "2_2") (pintype "passive"))
    )
    (net (code "36") (name "Net-(Q2-G)") (class "Default")
      (node (ref "D2") (pin "A") (pinfunction "A_A") (pintype "passive"))
      (node (ref "Q2") (pin "1") (pinfunction "G_1") (pintype "bidirectional"))
      (node (ref "R28") (pin "2") (pinfunction "2_2") (pintype "passive"))
      (node (ref "R30") (pin "1") (pinfunction "1_1") (pintype "passive"))
    )
    (net (code "37") (name "Net-(R17-Pad2)") (class "Default")
      (node (ref "R17") (pin "2") (pinfunction "2_2") (pintype "passive"))
      (node (ref "U$6") (pin "1") (pinfunction "1_1") (pintype "bidirectional"))
    )
    (net (code "38") (name "Net-(R18-Pad1)") (class "Default")
      (node (ref "R18") (pin "1") (pinfunction "1_1") (pintype "passive"))
      (node (ref "U$11") (pin "1") (pinfunction "1_1") (pintype "bidirectional"))
    )
    (net (code "39") (name "Net-(R29-Pad2)") (class "Default")
      (node (ref "R29") (pin "2") (pinfunction "2_2") (pintype "passive"))
      (node (ref "T1") (pin "B") (pinfunction "B_B") (pintype "passive"))
    )
    (net (code "40") (name "Net-(R30-Pad2)") (class "Default")
      (node (ref "R30") (pin "2") (pinfunction "2_2") (pintype "passive"))
      (node (ref "T1") (pin "C") (pinfunction "C_C") (pintype "passive"))
    )
    (net (code "41") (name "Net-(X1A-KL)") (class "Default")
      (node (ref "D1") (pin "A") (pinfunction "A_A") (pintype "passive"))
      (node (ref "X1") (pin "1") (pinfunction "KL_1") (pintype "passive"))
    )
    (net (code "42") (name "Net-(X7A-KL)") (class "Default")
      (node (ref "R14") (pin "1") (pinfunction "1_1") (pintype "passive"))
      (node (ref "X7") (pin "1") (pinfunction "KL_1") (pintype "passive"))
    )
    (net (code "43") (name "Net-(X7C-KL)") (class "Default")
      (node (ref "R15") (pin "1") (pinfunction "1_1") (pintype "passive"))
      (node (ref "X7") (pin "3") (pinfunction "KL_3") (pintype "passive"))
    )
    (net (code "44") (name "Net-(X7E-KL)") (class "Default")
      (node (ref "R16") (pin "1") (pinfunction "1_1") (pintype "passive"))
      (node (ref "X7") (pin "5") (pinfunction "KL_5") (pintype "passive"))
    )
    (net (code "45") (name "Net-(X8A-KL)") (class "Default")
      (node (ref "C20") (pin "1") (pinfunction "1_1") (pintype "passive"))
      (node (ref "R32") (pin "2") (pinfunction "2_2") (pintype "passive"))
      (node (ref "X8") (pin "1") (pinfunction "KL_1") (pintype "passive"))
    )
    (net (code "46") (name "Net-(X8B-KL)") (class "Default")
      (node (ref "C21") (pin "1") (pinfunction "1_1") (pintype "passive"))
      (node (ref "R35") (pin "2") (pinfunction "2_2") (pintype "passive"))
      (node (ref "X8") (pin "2") (pinfunction "KL_2") (pintype "passive"))
    )
    (net (code "47") (name "Net-(X9B-KL)") (class "Default")
      (node (ref "C14") (pin "1") (pinfunction "1_1") (pintype "passive"))
      (node (ref "LED11") (pin "C") (pinfunction "C_C") (pintype "passive"))
      (node (ref "R12") (pin "2") (pinfunction "2_2") (pintype "passive"))
      (node (ref "R13") (pin "1") (pinfunction "1_1") (pintype "passive"))
      (node (ref "X9") (pin "2") (pinfunction "KL_2") (pintype "passive"))
    )
    (net (code "48") (name "O_COOLANT_EN") (class "Default")
      (node (ref "IC3") (pin "26") (pinfunction "PC3(ADC3)_26") (pintype "bidirectional"))
      (node (ref "R29") (pin "1") (pinfunction "1_1") (pintype "passive"))
    )
    (net (code "49") (name "O_DIR_X") (class "Default")
      (node (ref "IC3") (pin "9") (pinfunction "PD5(T1)_9") (pintype "bidirectional"))
      (node (ref "X6") (pin "2") (pinfunction "KL_2") (pintype "passive"))
    )
    (net (code "50") (name "O_DIR_Y") (class "Default")
      (node (ref "IC3") (pin "10") (pinfunction "PD6(AIN0)_10") (pintype "bidirectional"))
      (node (ref "X2") (pin "2") (pinfunction "KL_2") (pintype "passive"))
    )
    (net (code "51") (name "O_DIR_Z") (class "Default")
      (node (ref "IC3") (pin "11") (pinfunction "PD7(AIN1)_11") (pintype "bidirectional"))
      (node (ref "X3") (pin "2") (pinfunction "KL_2") (pintype "passive"))
    )
    (net (code "52") (name "O_ENABLE") (class "Default")
      (node (ref "IC3") (pin "12") (pinfunction "PB0(ICP)_12") (pintype "bidirectional"))
      (node (ref "R34") (pin "2") (pinfunction "2_2") (pintype "passive"))
      (node (ref "X2") (pin "3") (pinfunction "KL_3") (pintype "passive"))
      (node (ref "X3") (pin "3") (pinfunction "KL_3") (pintype "passive"))
      (node (ref "X6") (pin "3") (pinfunction "KL_3") (pintype "passive"))
    )
    (net (code "53") (name "O_SPINDLE_DIR") (class "Default")
      (node (ref "IC3") (pin "17") (pinfunction "PB5(SCK)_17") (pintype "bidirectional"))
      (node (ref "R33") (pin "1") (pinfunction "1_1") (pintype "passive"))
      (node (ref "R35") (pin "1") (pinfunction "1_1") (pintype "passive"))
      (node (ref "R6") (pin "2") (pinfunction "2_2") (pintype "passive"))
    )
    (net (code "54") (name "O_SPINDLE_PWM") (class "Default")
      (node (ref "IC3") (pin "15") (pinfunction "PB3(MOSI/OC2)_15") (pintype "bidirectional"))
      (node (ref "R31") (pin "1") (pinfunction "1_1") (pintype "passive"))
      (node (ref "R32") (pin "1") (pinfunction "1_1") (pintype "passive"))
      (node (ref "R8") (pin "2") (pinfunction "2_2") (pintype "passive"))
    )
    (net (code "55") (name "O_STEP_X") (class "Default")
      (node (ref "IC3") (pin "32") (pinfunction "PD2(INT0)_32") (pintype "bidirectional"))
      (node (ref "R25") (pin "1") (pinfunction "1_1") (pintype "passive"))
      (node (ref "X6") (pin "1") (pinfunction "KL_1") (pintype "passive"))
    )
    (net (code "56") (name "O_STEP_Y") (class "Default")
      (node (ref "IC3") (pin "1") (pinfunction "PD3(INT1)_1") (pintype "bidirectional"))
      (node (ref "R26") (pin "1") (pinfunction "1_1") (pintype "passive"))
      (node (ref "X2") (pin "1") (pinfunction "KL_1") (pintype "passive"))
    )
    (net (code "57") (name "O_STEP_Z") (class "Default")
      (node (ref "IC3") (pin "2") (pinfunction "PD4(XCK/T0)_2") (pintype "bidirectional"))
      (node (ref "R27") (pin "1") (pinfunction "1_1") (pintype "passive"))
      (node (ref "X3") (pin "1") (pinfunction "KL_1") (pintype "passive"))
    )
    (net (code "58") (name "RX") (class "Default")
      (node (ref "IC3") (pin "30") (pinfunction "PD0(RXD)_30") (pintype "bidirectional"))
      (node (ref "JP2") (pin "2") (pinfunction "2_2") (pintype "passive"))
      (node (ref "LED4") (pin "C") (pinfunction "C_C") (pintype "passive"))
      (node (ref "R95") (pin "2") (pinfunction "2_2") (pintype "passive"))
      (node (ref "U$6") (pin "5") (pinfunction "5_5") (pintype "bidirectional"))
    )
    (net (code "59") (name "SCK") (class "Default")
      (node (ref "JP1") (pin "3") (pinfunction "3_3") (pintype "passive"))
      (node (ref "R6") (pin "1") (pinfunction "1_1") (pintype "passive"))
    )
    (net (code "60") (name "TX") (class "Default")
      (node (ref "IC3") (pin "31") (pinfunction "PD1(TXD)_31") (pintype "bidirectional"))
      (node (ref "JP2") (pin "3") (pinfunction "3_3") (pintype "passive"))
      (node (ref "LED3") (pin "C") (pinfunction "C_C") (pintype "passive"))
      (node (ref "U$11") (pin "3") (pinfunction "3_3") (pintype "bidirectional"))
    )
    (net (code "61") (name "USB_5V") (class "Default")
      (node (ref "C49") (pin "1") (pinfunction "1_1") (pintype "passive"))
      (node (ref "L4") (pin "1") (pinfunction "1_1") (pintype "passive"))
      (node (ref "X5") (pin "1") (pinfunction "1_1") (pintype "passive"))
    )
    (net (code "62") (name "USB_DM") (class "Default")
      (node (ref "R89") (pin "1") (pinfunction "1_1") (pintype "passive"))
      (node (ref "X5") (pin "2") (pinfunction "2_2") (pintype "passive"))
    )
    (net (code "63") (name "USB_DP") (class "Default")
      (node (ref "R64") (pin "1") (pinfunction "1_1") (pintype "passive"))
      (node (ref "X5") (pin "3") (pinfunction "3_3") (pintype "passive"))
    )
    (net (code "64") (name "USB_GND") (class "Default")
      (node (ref "C17") (pin "2") (pinfunction "2_2") (pintype "passive"))
      (node (ref "C49") (pin "2") (pinfunction "2_2") (pintype "passive"))
      (node (ref "C8") (pin "2") (pinfunction "2_2") (pintype "passive"))
      (node (ref "C9") (pin "2") (pinfunction "2_2") (pintype "passive"))
      (node (ref "IC11") (pin "13") (pinfunction "GND_13") (pintype "power_in"))
      (node (ref "IC11") (pin "5") (pinfunction "GND_5") (pintype "power_in"))
      (node (ref "U$11") (pin "4") (pinfunction "4_4") (pintype "bidirectional"))
      (node (ref "X5") (pin "5") (pinfunction "5_5") (pintype "passive"))
    )
    (net (code "65") (name "unconnected-(H2-MOUNT-PadB3,0)") (class "Default")
      (node (ref "H2") (pin "B3,0") (pinfunction "MOUNT_B3,0") (pintype "passive"))
    )
    (net (code "66") (name "unconnected-(IC3-ADC6-Pad19)") (class "Default")
      (node (ref "IC3") (pin "19") (pinfunction "ADC6_19") (pintype "bidirectional"))
    )
    (net (code "67") (name "unconnected-(IC3-ADC7-Pad22)") (class "Default")
      (node (ref "IC3") (pin "22") (pinfunction "ADC7_22") (pintype "bidirectional"))
    )
    (net (code "68") (name "unconnected-(IC3-PC4(ADC4{slash}SDA)-Pad27)") (class "Default")
      (node (ref "IC3") (pin "27") (pinfunction "PC4(ADC4/SDA)_27") (pintype "bidirectional"))
    )
    (net (code "69") (name "unconnected-(IC11-CBUS0-Pad15)") (class "Default")
      (node (ref "IC11") (pin "15") (pinfunction "CBUS0_15") (pintype "bidirectional"))
    )
    (net (code "70") (name "unconnected-(IC11-CBUS1-Pad14)") (class "Default")
      (node (ref "IC11") (pin "14") (pinfunction "CBUS1_14") (pintype "bidirectional"))
    )
    (net (code "71") (name "unconnected-(IC11-CBUS2-Pad7)") (class "Default")
      (node (ref "IC11") (pin "7") (pinfunction "CBUS2_7") (pintype "bidirectional"))
    )
    (net (code "72") (name "unconnected-(IC11-CBUS3-Pad16)") (class "Default")
      (node (ref "IC11") (pin "16") (pinfunction "CBUS3_16") (pintype "bidirectional"))
    )
    (net (code "73") (name "unconnected-(IC11-~{CTS}-Pad6)") (class "Default")
      (node (ref "IC11") (pin "6") (pinfunction "~{CTS}_6") (pintype "input"))
    )
    (net (code "74") (name "unconnected-(IC11-~{RTS}-Pad2)") (class "Default")
      (node (ref "IC11") (pin "2") (pinfunction "~{RTS}_2") (pintype "output"))
    )
    (net (code "75") (name "unconnected-(X5-Pad4)") (class "Default")
      (node (ref "X5") (pin "4") (pinfunction "4_4") (pintype "passive"))
    )
    (net (code "76") (name "~{RES}") (class "Default")
      (node (ref "C19") (pin "1") (pinfunction "1_1") (pintype "passive"))
      (node (ref "IC3") (pin "29") (pinfunction "PC6(/RESET)_29") (pintype "bidirectional"))
      (node (ref "JP1") (pin "5") (pinfunction "5_5") (pintype "passive"))
      (node (ref "R1") (pin "2") (pinfunction "2_2") (pintype "passive"))
      (node (ref "S1") (pin "1") (pinfunction "S_1") (pintype "passive"))
      (node (ref "S1") (pin "2") (pinfunction "S1_2") (pintype "passive"))
    )
  )
)
